# D1_-_TH_LCD_Dupont_RJ45.net
KiCad netlist of a schematic drawn in EAGLE
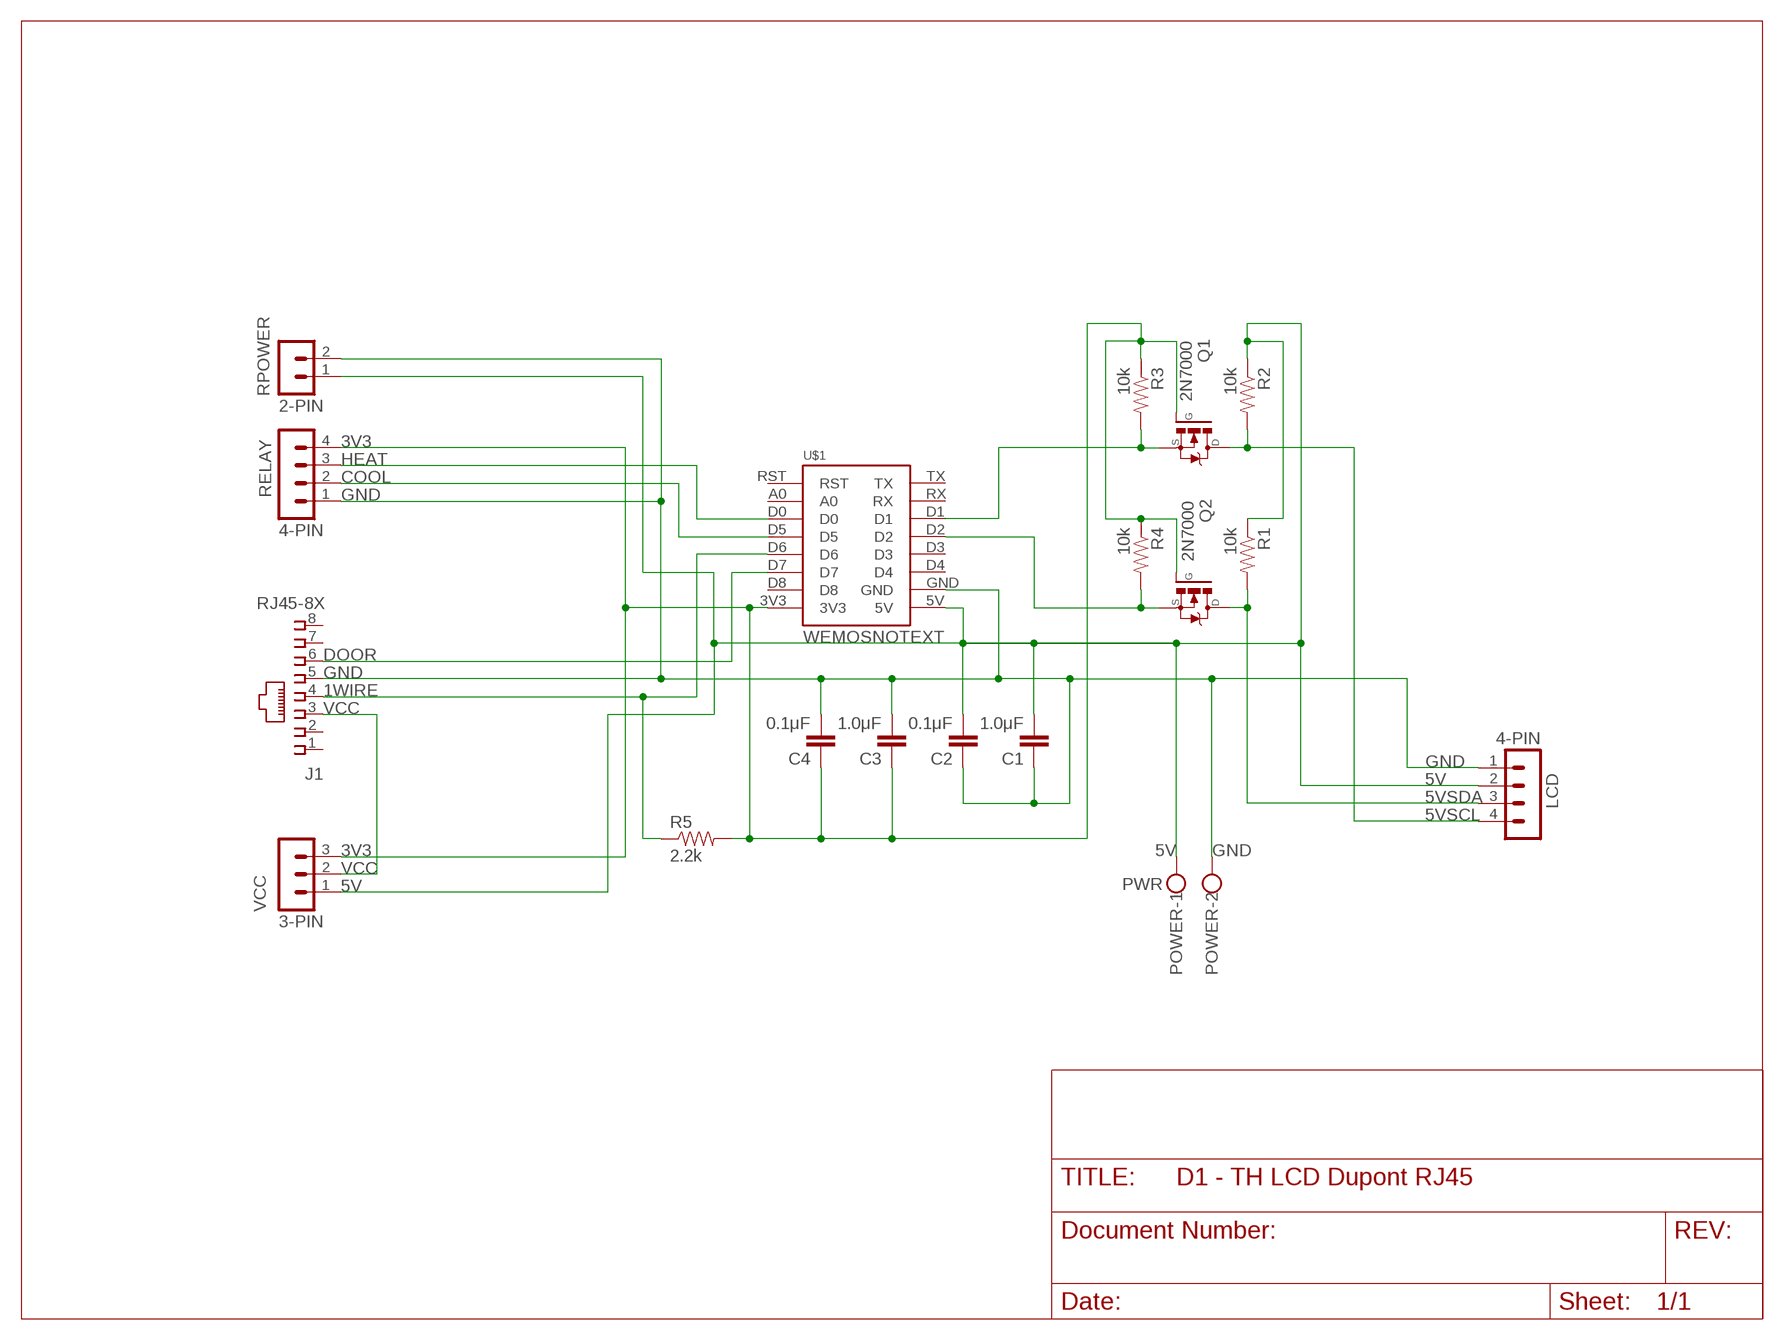
[diagram p0: schematic, sheet 1]

(export (version "E")
  (design (tool "Eeschema 10.0.6"))
  (components
    (comp (ref "C1")
      (value "1.0μF")
      (footprint "eagle-import:CAP_PTH-2.54")
      (libsource (lib "eagle-import") (part "CAP_CERAMIC_2.54"))
    )
    (comp (ref "C2")
      (value "0.1μF")
      (footprint "eagle-import:CAP_PTH-2.54")
      (libsource (lib "eagle-import") (part "CAP_CERAMIC_2.54"))
    )
    (comp (ref "C3")
      (value "1.0μF")
      (footprint "eagle-import:CAP_PTH-2.54")
      (libsource (lib "eagle-import") (part "CAP_CERAMIC_2.54"))
    )
    (comp (ref "C4")
      (value "0.1μF")
      (footprint "eagle-import:CAP_PTH-2.54")
      (libsource (lib "eagle-import") (part "CAP_CERAMIC_2.54"))
    )
    (comp (ref "J1")
      (value "RJ45-8X")
      (footprint "eagle-import:RJ45-NO-SHIELD-NOLINE")
      (libsource (lib "eagle-import") (part "RJ45-8X"))
    )
    (comp (ref "LCD")
      (value "4-PIN")
      (footprint "eagle-import:HDR-4_VERT")
      (libsource (lib "eagle-import") (part "HDR-4"))
    )
    (comp (ref "POWER")
      (value "PWR")
      (footprint "eagle-import:W237-102")
      (fields (field (name "MPN") "237-102"))
      (libsource (lib "eagle-import") (part "W237-102"))
    )
    (comp (ref "Q1")
      (value "2N7000")
      (footprint "eagle-import:TO-92")
      (libsource (lib "eagle-import") (part "2N7000"))
    )
    (comp (ref "Q2")
      (value "2N7000")
      (footprint "eagle-import:TO-92")
      (libsource (lib "eagle-import") (part "2N7000"))
    )
    (comp (ref "R1")
      (value "10k")
      (footprint "eagle-import:AXIAL-0.3")
      (libsource (lib "eagle-import") (part "10KOHM-HORIZ-1/4W-1%"))
    )
    (comp (ref "R2")
      (value "10k")
      (footprint "eagle-import:AXIAL-0.3")
      (libsource (lib "eagle-import") (part "10KOHM-HORIZ-1/4W-1%"))
    )
    (comp (ref "R3")
      (value "10k")
      (footprint "eagle-import:AXIAL-0.3")
      (libsource (lib "eagle-import") (part "10KOHM-HORIZ-1/4W-1%"))
    )
    (comp (ref "R4")
      (value "10k")
      (footprint "eagle-import:AXIAL-0.3")
      (libsource (lib "eagle-import") (part "10KOHM-HORIZ-1/4W-1%"))
    )
    (comp (ref "R5")
      (value "2.2k")
      (footprint "eagle-import:AXIAL-0.3")
      (libsource (lib "eagle-import") (part "10KOHM-HORIZ-1/4W-1%"))
    )
    (comp (ref "RELAY")
      (value "4-PIN")
      (footprint "eagle-import:HDR-4_VERT")
      (libsource (lib "eagle-import") (part "HDR-4"))
    )
    (comp (ref "RPOWER")
      (value "2-PIN")
      (footprint "eagle-import:HDR-2_VERT")
      (libsource (lib "eagle-import") (part "HDR-2"))
    )
    (comp (ref "U$1")
      (value "WEMOSNOTEXT")
      (footprint "eagle-import:WEMOS_D1-NOTEXT")
      (libsource (lib "eagle-import") (part "WEMOSNOTEXT"))
    )
    (comp (ref "VCC")
      (value "3-PIN")
      (footprint "eagle-import:MA03-1")
      (libsource (lib "eagle-import") (part "MA03-1"))
    )
  )
  (nets
    (net (code "1") (name "/1WIRE") (class "Default")
      (node (ref "J1") (pin "4") (pinfunction "4_4") (pintype "passive"))
      (node (ref "R5") (pin "P$1") (pinfunction "1_P$1") (pintype "passive"))
      (node (ref "U$1") (pin "D6") (pinfunction "D6_D6") (pintype "bidirectional"))
    )
    (net (code "2") (name "/3V3") (class "Default")
      (node (ref "C3") (pin "1") (pinfunction "1_1") (pintype "passive"))
      (node (ref "C4") (pin "1") (pinfunction "1_1") (pintype "passive"))
      (node (ref "Q1") (pin "2") (pinfunction "G_2") (pintype "passive"))
      (node (ref "Q2") (pin "2") (pinfunction "G_2") (pintype "passive"))
      (node (ref "R3") (pin "P$1") (pinfunction "1_P$1") (pintype "passive"))
      (node (ref "R4") (pin "P$1") (pinfunction "1_P$1") (pintype "passive"))
      (node (ref "R5") (pin "P$2") (pinfunction "2_P$2") (pintype "passive"))
      (node (ref "RELAY") (pin "4") (pinfunction "4_4") (pintype "passive"))
      (node (ref "U$1") (pin "3V3") (pinfunction "3V3_3V3") (pintype "bidirectional"))
      (node (ref "VCC") (pin "3") (pinfunction "3_3") (pintype "passive"))
    )
    (net (code "3") (name "/5V") (class "Default")
      (node (ref "C1") (pin "2") (pinfunction "2_2") (pintype "passive"))
      (node (ref "C2") (pin "2") (pinfunction "2_2") (pintype "passive"))
      (node (ref "LCD") (pin "2") (pinfunction "2_2") (pintype "passive"))
      (node (ref "POWER") (pin "1") (pinfunction "KL_1") (pintype "passive"))
      (node (ref "R1") (pin "P$1") (pinfunction "1_P$1") (pintype "passive"))
      (node (ref "R2") (pin "P$1") (pinfunction "1_P$1") (pintype "passive"))
      (node (ref "RPOWER") (pin "1") (pinfunction "1_1") (pintype "passive"))
      (node (ref "U$1") (pin "5V") (pinfunction "5V_5V") (pintype "bidirectional"))
      (node (ref "VCC") (pin "1") (pinfunction "1_1") (pintype "passive"))
    )
    (net (code "4") (name "/5VSCL") (class "Default")
      (node (ref "LCD") (pin "4") (pinfunction "4_4") (pintype "passive"))
      (node (ref "Q1") (pin "3") (pinfunction "D_3") (pintype "passive"))
      (node (ref "R2") (pin "P$2") (pinfunction "2_P$2") (pintype "passive"))
    )
    (net (code "5") (name "/5VSDA") (class "Default")
      (node (ref "LCD") (pin "3") (pinfunction "3_3") (pintype "passive"))
      (node (ref "Q2") (pin "3") (pinfunction "D_3") (pintype "passive"))
      (node (ref "R1") (pin "P$2") (pinfunction "2_P$2") (pintype "passive"))
    )
    (net (code "6") (name "/COOL") (class "Default")
      (node (ref "RELAY") (pin "2") (pinfunction "2_2") (pintype "passive"))
      (node (ref "U$1") (pin "D5") (pinfunction "D5_D5") (pintype "bidirectional"))
    )
    (net (code "7") (name "/DOOR") (class "Default")
      (node (ref "J1") (pin "6") (pinfunction "6_6") (pintype "passive"))
      (node (ref "U$1") (pin "D7") (pinfunction "D7_D7") (pintype "bidirectional"))
    )
    (net (code "8") (name "/GND") (class "Default")
      (node (ref "C1") (pin "1") (pinfunction "1_1") (pintype "passive"))
      (node (ref "C2") (pin "1") (pinfunction "1_1") (pintype "passive"))
      (node (ref "C3") (pin "2") (pinfunction "2_2") (pintype "passive"))
      (node (ref "C4") (pin "2") (pinfunction "2_2") (pintype "passive"))
      (node (ref "J1") (pin "5") (pinfunction "5_5") (pintype "passive"))
      (node (ref "LCD") (pin "1") (pinfunction "1_1") (pintype "passive"))
      (node (ref "POWER") (pin "2") (pinfunction "KL_2") (pintype "passive"))
      (node (ref "RELAY") (pin "1") (pinfunction "1_1") (pintype "passive"))
      (node (ref "RPOWER") (pin "2") (pinfunction "2_2") (pintype "passive"))
      (node (ref "U$1") (pin "GND") (pinfunction "GND_GND") (pintype "bidirectional"))
    )
    (net (code "9") (name "/HEAT") (class "Default")
      (node (ref "RELAY") (pin "3") (pinfunction "3_3") (pintype "passive"))
      (node (ref "U$1") (pin "D0") (pinfunction "D0_D0") (pintype "bidirectional"))
    )
    (net (code "10") (name "/VCC") (class "Default")
      (node (ref "J1") (pin "3") (pinfunction "3_3") (pintype "passive"))
      (node (ref "VCC") (pin "2") (pinfunction "2_2") (pintype "passive"))
    )
    (net (code "11") (name "Net-(Q1-S)") (class "Default")
      (node (ref "Q1") (pin "1") (pinfunction "S_1") (pintype "passive"))
      (node (ref "R3") (pin "P$2") (pinfunction "2_P$2") (pintype "passive"))
      (node (ref "U$1") (pin "D1") (pinfunction "D1_D1") (pintype "bidirectional"))
    )
    (net (code "12") (name "Net-(Q2-S)") (class "Default")
      (node (ref "Q2") (pin "1") (pinfunction "S_1") (pintype "passive"))
      (node (ref "R4") (pin "P$2") (pinfunction "2_P$2") (pintype "passive"))
      (node (ref "U$1") (pin "D2") (pinfunction "D2_D2") (pintype "bidirectional"))
    )
    (net (code "13") (name "unconnected-(J1-Pad1)") (class "Default")
      (node (ref "J1") (pin "1") (pinfunction "1_1") (pintype "passive"))
    )
    (net (code "14") (name "unconnected-(J1-Pad2)") (class "Default")
      (node (ref "J1") (pin "2") (pinfunction "2_2") (pintype "passive"))
    )
    (net (code "15") (name "unconnected-(J1-Pad7)") (class "Default")
      (node (ref "J1") (pin "7") (pinfunction "7_7") (pintype "passive"))
    )
    (net (code "16") (name "unconnected-(J1-Pad8)") (class "Default")
      (node (ref "J1") (pin "8") (pinfunction "8_8") (pintype "passive"))
    )
    (net (code "17") (name "unconnected-(U$1-PadA0)") (class "Default")
      (node (ref "U$1") (pin "A0") (pinfunction "A0_A0") (pintype "bidirectional"))
    )
    (net (code "18") (name "unconnected-(U$1-PadD3)") (class "Default")
      (node (ref "U$1") (pin "D3") (pinfunction "D3_D3") (pintype "bidirectional"))
    )
    (net (code "19") (name "unconnected-(U$1-PadD4)") (class "Default")
      (node (ref "U$1") (pin "D4") (pinfunction "D4_D4") (pintype "bidirectional"))
    )
    (net (code "20") (name "unconnected-(U$1-PadD8)") (class "Default")
      (node (ref "U$1") (pin "D8") (pinfunction "D8_D8") (pintype "bidirectional"))
    )
    (net (code "21") (name "unconnected-(U$1-PadRST)") (class "Default")
      (node (ref "U$1") (pin "RST") (pinfunction "RST_RST") (pintype "bidirectional"))
    )
    (net (code "22") (name "unconnected-(U$1-PadRX)") (class "Default")
      (node (ref "U$1") (pin "RX") (pinfunction "RX_RX") (pintype "bidirectional"))
    )
    (net (code "23") (name "unconnected-(U$1-PadTX)") (class "Default")
      (node (ref "U$1") (pin "TX") (pinfunction "TX_TX") (pintype "bidirectional"))
    )
  )
)
